# stabs.net
KiCad netlist of a schematic drawn in Altium Designer
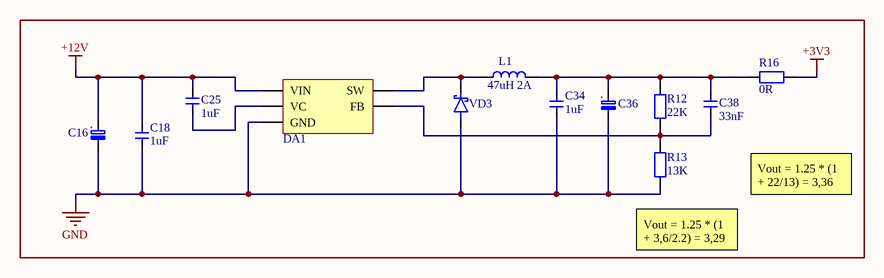
[diagram p0: stabs.SchDoc]

(export (version "E")
  (design (tool "Eeschema 10.0.6"))
  (components
    (comp (ref "C16")
      (value "25V 220uF")
      (footprint "D8C3.2H12")
      (description "Electrolytic Cap")
      (libsource (lib "GKirik") (part "Cap Aluminum"))
    )
    (comp (ref "C18")
      (value "1uF")
      (footprint "CAP0805")
      (description "Ceramic SMD Cap")
      (libsource (lib "Asterisk") (part "CAP Ceramic"))
    )
    (comp (ref "C25")
      (value "1uF")
      (footprint "CAP0805")
      (description "Ceramic SMD Cap")
      (libsource (lib "Asterisk") (part "CAP Ceramic"))
    )
    (comp (ref "C34")
      (value "1uF")
      (footprint "CAP0805")
      (description "Ceramic SMD Cap")
      (libsource (lib "Asterisk") (part "CAP Ceramic"))
    )
    (comp (ref "C36")
      (value "10V 330uF")
      (footprint "D10C4.4H10")
      (description "Electrolytic Cap")
      (libsource (lib "GKirik") (part "Cap Aluminum"))
    )
    (comp (ref "C38")
      (value "33nF")
      (footprint "CAP0805")
      (description "Ceramic SMD Cap")
      (libsource (lib "Asterisk") (part "CAP Ceramic"))
    )
    (comp (ref "DA1")
      (value "XL4015")
      (footprint "TO263-5L")
      (description "Buck converter")
      (libsource (lib "Asterisk") (part "XL4015"))
    )
    (comp (ref "L1")
      (value "47uH 2A")
      (footprint "IND: B82477G")
      (description "Inductance")
      (libsource (lib "GKirik") (part "Inductor"))
    )
    (comp (ref "R12")
      (value "22K")
      (footprint "RES0805")
      (description "RES smd")
      (libsource (lib "Asterisk") (part "RES"))
    )
    (comp (ref "R13")
      (value "13K")
      (footprint "RES0805")
      (description "RES smd")
      (libsource (lib "Asterisk") (part "RES"))
    )
    (comp (ref "R16")
      (value "0R")
      (footprint "RES1206")
      (description "RES smd")
      (libsource (lib "Asterisk") (part "RES"))
    )
    (comp (ref "VD3")
      (value "~")
      (footprint "DO-214AC (SMA)")
      (description "Diode Schottky")
      (libsource (lib "Asterisk") (part "Diode Schottky"))
    )
  )
  (nets
    (net (code "1") (name "+3V3") (class "Default")
      (node (ref "R16") (pin "2") (pinfunction "2_2") (pintype "passive"))
    )
    (net (code "2") (name "+12V") (class "Default")
      (node (ref "C16") (pin "1") (pinfunction "PLUS_1") (pintype "passive"))
      (node (ref "C18") (pin "2") (pinfunction "2_2") (pintype "passive"))
      (node (ref "C25") (pin "2") (pinfunction "2_2") (pintype "passive"))
      (node (ref "DA1") (pin "5") (pinfunction "VIN_5") (pintype "passive"))
    )
    (net (code "3") (name "GND") (class "Default")
      (node (ref "C16") (pin "2") (pinfunction "MINUS_2") (pintype "passive"))
      (node (ref "C18") (pin "1") (pinfunction "1_1") (pintype "passive"))
      (node (ref "C34") (pin "1") (pinfunction "1_1") (pintype "passive"))
      (node (ref "C36") (pin "2") (pinfunction "MINUS_2") (pintype "passive"))
      (node (ref "DA1") (pin "1") (pinfunction "GND_1") (pintype "passive"))
      (node (ref "R13") (pin "1") (pinfunction "1_1") (pintype "passive"))
      (node (ref "VD3") (pin "A") (pinfunction "A_A") (pintype "passive"))
    )
    (net (code "4") (name "Net-(C36-PLUS)") (class "Default")
      (node (ref "C34") (pin "2") (pinfunction "2_2") (pintype "passive"))
      (node (ref "C36") (pin "1") (pinfunction "PLUS_1") (pintype "passive"))
      (node (ref "C38") (pin "2") (pinfunction "2_2") (pintype "passive"))
      (node (ref "L1") (pin "2") (pinfunction "2_2") (pintype "passive"))
      (node (ref "R12") (pin "2") (pinfunction "2_2") (pintype "passive"))
      (node (ref "R16") (pin "1") (pinfunction "1_1") (pintype "passive"))
    )
    (net (code "5") (name "Net-(DA1-FB)") (class "Default")
      (node (ref "C38") (pin "1") (pinfunction "1_1") (pintype "passive"))
      (node (ref "DA1") (pin "2") (pinfunction "FB_2") (pintype "passive"))
      (node (ref "R12") (pin "1") (pinfunction "1_1") (pintype "passive"))
      (node (ref "R13") (pin "2") (pinfunction "2_2") (pintype "passive"))
    )
    (net (code "6") (name "Net-(DA1-SW)") (class "Default")
      (node (ref "DA1") (pin "3") (pinfunction "SW_3") (pintype "passive"))
      (node (ref "L1") (pin "1") (pinfunction "1_1") (pintype "passive"))
      (node (ref "VD3") (pin "K") (pinfunction "K_K") (pintype "passive"))
    )
    (net (code "7") (name "Net-(DA1-VC)") (class "Default")
      (node (ref "C25") (pin "1") (pinfunction "1_1") (pintype "passive"))
      (node (ref "DA1") (pin "4") (pinfunction "VC_4") (pintype "passive"))
    )
  )
)
